# GPIO.net
KiCad netlist of a schematic drawn in Altium Designer
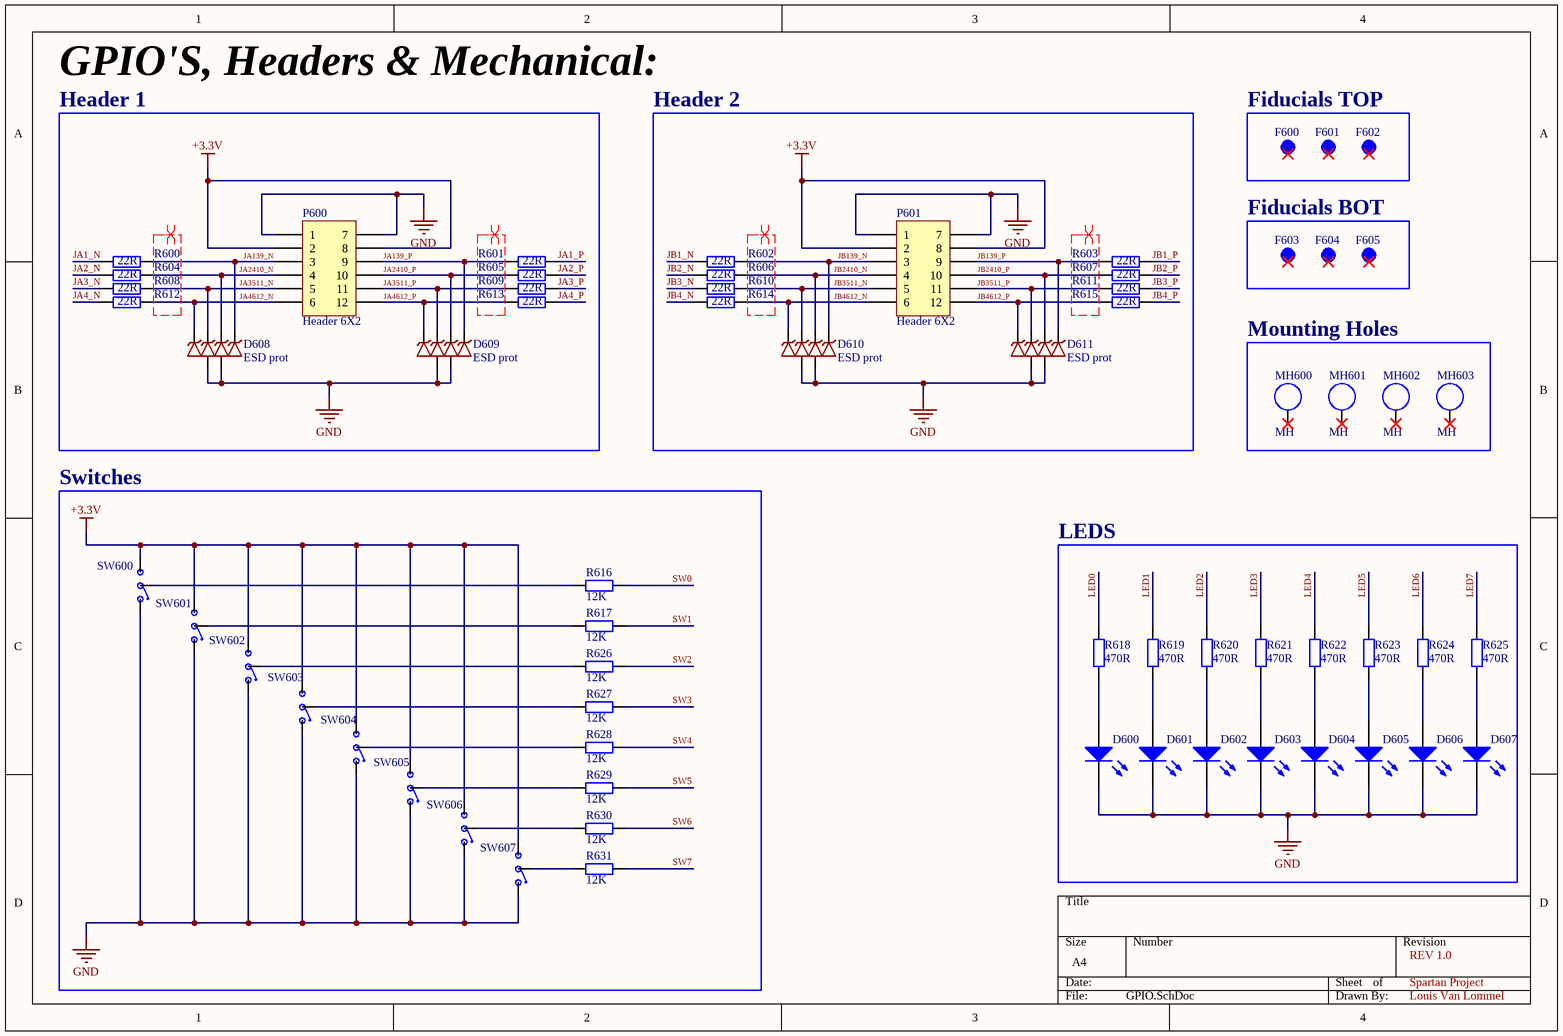
[diagram p0: GPIO.SchDoc]

(export (version "E")
  (design (tool "Eeschema 10.0.6"))
  (components
    (comp (ref "D600")
      (value "LED")
      (footprint "LED_0603")
      (description "Typical INFRARED GaAs LED")
      (fields (field (name "PUBLISHER") "Altium Limited"))
      (libsource (lib "Miscellaneous Devices") (part "LED0"))
    )
    (comp (ref "D601")
      (value "LED")
      (footprint "LED_0603")
      (description "Typical INFRARED GaAs LED")
      (fields (field (name "PUBLISHER") "Altium Limited"))
      (libsource (lib "Miscellaneous Devices") (part "LED0"))
    )
    (comp (ref "D602")
      (value "LED")
      (footprint "LED_0603")
      (description "Typical INFRARED GaAs LED")
      (fields (field (name "PUBLISHER") "Altium Limited"))
      (libsource (lib "Miscellaneous Devices") (part "LED0"))
    )
    (comp (ref "D603")
      (value "LED")
      (footprint "LED_0603")
      (description "Typical INFRARED GaAs LED")
      (fields (field (name "PUBLISHER") "Altium Limited"))
      (libsource (lib "Miscellaneous Devices") (part "LED0"))
    )
    (comp (ref "D604")
      (value "LED")
      (footprint "LED_0603")
      (description "Typical INFRARED GaAs LED")
      (fields (field (name "PUBLISHER") "Altium Limited"))
      (libsource (lib "Miscellaneous Devices") (part "LED0"))
    )
    (comp (ref "D605")
      (value "LED")
      (footprint "LED_0603")
      (description "Typical INFRARED GaAs LED")
      (fields (field (name "PUBLISHER") "Altium Limited"))
      (libsource (lib "Miscellaneous Devices") (part "LED0"))
    )
    (comp (ref "D606")
      (value "LED")
      (footprint "LED_0603")
      (description "Typical INFRARED GaAs LED")
      (fields (field (name "PUBLISHER") "Altium Limited"))
      (libsource (lib "Miscellaneous Devices") (part "LED0"))
    )
    (comp (ref "D607")
      (value "LED")
      (footprint "LED_0603")
      (description "Typical INFRARED GaAs LED")
      (fields (field (name "PUBLISHER") "Altium Limited"))
      (libsource (lib "Miscellaneous Devices") (part "LED0"))
    )
    (comp (ref "D608")
      (value "ESD prot")
      (footprint "SOT457")
      (description "NEXPERIA BZA462A,125")
      (libsource (lib "Schematic_Symbols") (part "ESD prot"))
    )
    (comp (ref "D609")
      (value "ESD prot")
      (footprint "SOT457")
      (description "NEXPERIA BZA462A,125")
      (libsource (lib "Schematic_Symbols") (part "ESD prot"))
    )
    (comp (ref "D610")
      (value "ESD prot")
      (footprint "SOT457")
      (description "NEXPERIA BZA462A,125")
      (libsource (lib "Schematic_Symbols") (part "ESD prot"))
    )
    (comp (ref "D611")
      (value "ESD prot")
      (footprint "SOT457")
      (description "NEXPERIA BZA462A,125")
      (libsource (lib "Schematic_Symbols") (part "ESD prot"))
    )
    (comp (ref "F600")
      (value "Fiducial")
      (footprint "Fiducial30mil")
      (description "30mil Fiducial")
      (libsource (lib "Schematic_Symbols") (part "Fiducial"))
    )
    (comp (ref "F601")
      (value "Fiducial")
      (footprint "Fiducial30mil")
      (description "30mil Fiducial")
      (libsource (lib "Schematic_Symbols") (part "Fiducial"))
    )
    (comp (ref "F602")
      (value "Fiducial")
      (footprint "Fiducial30mil")
      (description "30mil Fiducial")
      (libsource (lib "Schematic_Symbols") (part "Fiducial"))
    )
    (comp (ref "F603")
      (value "Fiducial")
      (footprint "Fiducial30mil")
      (description "30mil Fiducial")
      (libsource (lib "Schematic_Symbols") (part "Fiducial"))
    )
    (comp (ref "F604")
      (value "Fiducial")
      (footprint "Fiducial30mil")
      (description "30mil Fiducial")
      (libsource (lib "Schematic_Symbols") (part "Fiducial"))
    )
    (comp (ref "F605")
      (value "Fiducial")
      (footprint "Fiducial30mil")
      (description "30mil Fiducial")
      (libsource (lib "Schematic_Symbols") (part "Fiducial"))
    )
    (comp (ref "MH600")
      (value "MH")
      (footprint "MH3.2mm")
      (description "3.2mm mounting hole")
      (libsource (lib "Schematic_Symbols") (part "MH"))
    )
    (comp (ref "MH601")
      (value "MH")
      (footprint "MH3.2mm")
      (description "3.2mm mounting hole")
      (libsource (lib "Schematic_Symbols") (part "MH"))
    )
    (comp (ref "MH602")
      (value "MH")
      (footprint "MH3.2mm")
      (description "3.2mm mounting hole")
      (libsource (lib "Schematic_Symbols") (part "MH"))
    )
    (comp (ref "MH603")
      (value "MH")
      (footprint "MH3.2mm")
      (description "3.2mm mounting hole")
      (libsource (lib "Schematic_Symbols") (part "MH"))
    )
    (comp (ref "P600")
      (value "Header 6X2")
      (footprint "HDR2X6_CEN")
      (description "Header, 6-Pin, Dual row")
      (fields (field (name "PUBLISHER") "Altium Limited"))
      (libsource (lib "Miscellaneous Connectors") (part "Header 6X2A"))
    )
    (comp (ref "P601")
      (value "Header 6X2")
      (footprint "HDR2X6_CEN")
      (description "Header, 6-Pin, Dual row")
      (fields (field (name "PUBLISHER") "Altium Limited"))
      (libsource (lib "Miscellaneous Connectors") (part "Header 6X2A"))
    )
    (comp (ref "R600")
      (value "22R")
      (footprint "RES_0603")
      (description "Resistor")
      (fields (field (name "Comment") "22") (field (name "PUBLISHER") "Altium Limited"))
      (libsource (lib "Miscellaneous Devices") (part "Res2"))
    )
    (comp (ref "R601")
      (value "22R")
      (footprint "RES_0603")
      (description "Resistor")
      (fields (field (name "Comment") "22") (field (name "PUBLISHER") "Altium Limited"))
      (libsource (lib "Miscellaneous Devices") (part "Res2"))
    )
    (comp (ref "R602")
      (value "22R")
      (footprint "RES_0603")
      (description "Resistor")
      (fields (field (name "Comment") "22") (field (name "PUBLISHER") "Altium Limited"))
      (libsource (lib "Miscellaneous Devices") (part "Res2"))
    )
    (comp (ref "R603")
      (value "22R")
      (footprint "RES_0603")
      (description "Resistor")
      (fields (field (name "Comment") "22") (field (name "PUBLISHER") "Altium Limited"))
      (libsource (lib "Miscellaneous Devices") (part "Res2"))
    )
    (comp (ref "R604")
      (value "22R")
      (footprint "RES_0603")
      (description "Resistor")
      (fields (field (name "Comment") "22") (field (name "PUBLISHER") "Altium Limited"))
      (libsource (lib "Miscellaneous Devices") (part "Res2"))
    )
    (comp (ref "R605")
      (value "22R")
      (footprint "RES_0603")
      (description "Resistor")
      (fields (field (name "Comment") "22") (field (name "PUBLISHER") "Altium Limited"))
      (libsource (lib "Miscellaneous Devices") (part "Res2"))
    )
    (comp (ref "R606")
      (value "22R")
      (footprint "RES_0603")
      (description "Resistor")
      (fields (field (name "Comment") "22") (field (name "PUBLISHER") "Altium Limited"))
      (libsource (lib "Miscellaneous Devices") (part "Res2"))
    )
    (comp (ref "R607")
      (value "22R")
      (footprint "RES_0603")
      (description "Resistor")
      (fields (field (name "Comment") "22") (field (name "PUBLISHER") "Altium Limited"))
      (libsource (lib "Miscellaneous Devices") (part "Res2"))
    )
    (comp (ref "R608")
      (value "22R")
      (footprint "RES_0603")
      (description "Resistor")
      (fields (field (name "Comment") "22") (field (name "PUBLISHER") "Altium Limited"))
      (libsource (lib "Miscellaneous Devices") (part "Res2"))
    )
    (comp (ref "R609")
      (value "22R")
      (footprint "RES_0603")
      (description "Resistor")
      (fields (field (name "Comment") "22") (field (name "PUBLISHER") "Altium Limited"))
      (libsource (lib "Miscellaneous Devices") (part "Res2"))
    )
    (comp (ref "R610")
      (value "22R")
      (footprint "RES_0603")
      (description "Resistor")
      (fields (field (name "Comment") "22") (field (name "PUBLISHER") "Altium Limited"))
      (libsource (lib "Miscellaneous Devices") (part "Res2"))
    )
    (comp (ref "R611")
      (value "22R")
      (footprint "RES_0603")
      (description "Resistor")
      (fields (field (name "Comment") "22") (field (name "PUBLISHER") "Altium Limited"))
      (libsource (lib "Miscellaneous Devices") (part "Res2"))
    )
    (comp (ref "R612")
      (value "22R")
      (footprint "RES_0603")
      (description "Resistor")
      (fields (field (name "Comment") "22") (field (name "PUBLISHER") "Altium Limited"))
      (libsource (lib "Miscellaneous Devices") (part "Res2"))
    )
    (comp (ref "R613")
      (value "22R")
      (footprint "RES_0603")
      (description "Resistor")
      (fields (field (name "Comment") "22") (field (name "PUBLISHER") "Altium Limited"))
      (libsource (lib "Miscellaneous Devices") (part "Res2"))
    )
    (comp (ref "R614")
      (value "22R")
      (footprint "RES_0603")
      (description "Resistor")
      (fields (field (name "Comment") "22") (field (name "PUBLISHER") "Altium Limited"))
      (libsource (lib "Miscellaneous Devices") (part "Res2"))
    )
    (comp (ref "R615")
      (value "22R")
      (footprint "RES_0603")
      (description "Resistor")
      (fields (field (name "Comment") "22") (field (name "PUBLISHER") "Altium Limited"))
      (libsource (lib "Miscellaneous Devices") (part "Res2"))
    )
    (comp (ref "R616")
      (value "12K")
      (footprint "RES_0603")
      (description "Resistor")
      (fields (field (name "PUBLISHER") "Altium Limited"))
      (libsource (lib "Miscellaneous Devices") (part "Res2"))
    )
    (comp (ref "R617")
      (value "12K")
      (footprint "RES_0603")
      (description "Resistor")
      (fields (field (name "PUBLISHER") "Altium Limited"))
      (libsource (lib "Miscellaneous Devices") (part "Res2"))
    )
    (comp (ref "R618")
      (value "470R")
      (footprint "RES_0603")
      (description "Resistor")
      (fields (field (name "Comment") "470") (field (name "PUBLISHER") "Altium Limited"))
      (libsource (lib "") (part "Res2_1"))
    )
    (comp (ref "R619")
      (value "470R")
      (footprint "RES_0603")
      (description "Resistor")
      (fields (field (name "Comment") "470") (field (name "PUBLISHER") "Altium Limited"))
      (libsource (lib "") (part "Res2_1"))
    )
    (comp (ref "R620")
      (value "470R")
      (footprint "RES_0603")
      (description "Resistor")
      (fields (field (name "Comment") "470") (field (name "PUBLISHER") "Altium Limited"))
      (libsource (lib "") (part "Res2_1"))
    )
    (comp (ref "R621")
      (value "470R")
      (footprint "RES_0603")
      (description "Resistor")
      (fields (field (name "Comment") "470") (field (name "PUBLISHER") "Altium Limited"))
      (libsource (lib "") (part "Res2_1"))
    )
    (comp (ref "R622")
      (value "470R")
      (footprint "RES_0603")
      (description "Resistor")
      (fields (field (name "Comment") "470") (field (name "PUBLISHER") "Altium Limited"))
      (libsource (lib "") (part "Res2_1"))
    )
    (comp (ref "R623")
      (value "470R")
      (footprint "RES_0603")
      (description "Resistor")
      (fields (field (name "Comment") "470") (field (name "PUBLISHER") "Altium Limited"))
      (libsource (lib "") (part "Res2_1"))
    )
    (comp (ref "R624")
      (value "470R")
      (footprint "RES_0603")
      (description "Resistor")
      (fields (field (name "Comment") "470") (field (name "PUBLISHER") "Altium Limited"))
      (libsource (lib "") (part "Res2_1"))
    )
    (comp (ref "R625")
      (value "470R")
      (footprint "RES_0603")
      (description "Resistor")
      (fields (field (name "Comment") "470") (field (name "PUBLISHER") "Altium Limited"))
      (libsource (lib "") (part "Res2_1"))
    )
    (comp (ref "R626")
      (value "12K")
      (footprint "RES_0603")
      (description "Resistor")
      (fields (field (name "PUBLISHER") "Altium Limited"))
      (libsource (lib "Miscellaneous Devices") (part "Res2"))
    )
    (comp (ref "R627")
      (value "12K")
      (footprint "RES_0603")
      (description "Resistor")
      (fields (field (name "PUBLISHER") "Altium Limited"))
      (libsource (lib "Miscellaneous Devices") (part "Res2"))
    )
    (comp (ref "R628")
      (value "12K")
      (footprint "RES_0603")
      (description "Resistor")
      (fields (field (name "PUBLISHER") "Altium Limited"))
      (libsource (lib "Miscellaneous Devices") (part "Res2"))
    )
    (comp (ref "R629")
      (value "12K")
      (footprint "RES_0603")
      (description "Resistor")
      (fields (field (name "PUBLISHER") "Altium Limited"))
      (libsource (lib "Miscellaneous Devices") (part "Res2"))
    )
    (comp (ref "R630")
      (value "12K")
      (footprint "RES_0603")
      (description "Resistor")
      (fields (field (name "PUBLISHER") "Altium Limited"))
      (libsource (lib "Miscellaneous Devices") (part "Res2"))
    )
    (comp (ref "R631")
      (value "12K")
      (footprint "RES_0603")
      (description "Resistor")
      (fields (field (name "PUBLISHER") "Altium Limited"))
      (libsource (lib "Miscellaneous Devices") (part "Res2"))
    )
    (comp (ref "SW600")
      (value "SPDT SW")
      (footprint "SPDT SWITCH")
      (libsource (lib "Schematic_Symbols") (part "SPDT SW"))
    )
    (comp (ref "SW601")
      (value "SPDT SW")
      (footprint "SPDT SWITCH")
      (libsource (lib "Schematic_Symbols") (part "SPDT SW"))
    )
    (comp (ref "SW602")
      (value "SPDT SW")
      (footprint "SPDT SWITCH")
      (libsource (lib "Schematic_Symbols") (part "SPDT SW"))
    )
    (comp (ref "SW603")
      (value "SPDT SW")
      (footprint "SPDT SWITCH")
      (libsource (lib "Schematic_Symbols") (part "SPDT SW"))
    )
    (comp (ref "SW604")
      (value "SPDT SW")
      (footprint "SPDT SWITCH")
      (libsource (lib "Schematic_Symbols") (part "SPDT SW"))
    )
    (comp (ref "SW605")
      (value "SPDT SW")
      (footprint "SPDT SWITCH")
      (libsource (lib "Schematic_Symbols") (part "SPDT SW"))
    )
    (comp (ref "SW606")
      (value "SPDT SW")
      (footprint "SPDT SWITCH")
      (libsource (lib "Schematic_Symbols") (part "SPDT SW"))
    )
    (comp (ref "SW607")
      (value "SPDT SW")
      (footprint "SPDT SWITCH")
      (libsource (lib "Schematic_Symbols") (part "SPDT SW"))
    )
  )
  (nets
    (net (code "1") (name "+3.3V") (class "Default")
      (node (ref "P600") (pin "2") (pinfunction "2_2") (pintype "passive"))
      (node (ref "P600") (pin "8") (pinfunction "8_8") (pintype "passive"))
      (node (ref "P601") (pin "2") (pinfunction "2_2") (pintype "passive"))
      (node (ref "P601") (pin "8") (pinfunction "8_8") (pintype "passive"))
      (node (ref "SW600") (pin "1") (pinfunction "1_1") (pintype "passive"))
      (node (ref "SW601") (pin "1") (pinfunction "1_1") (pintype "passive"))
      (node (ref "SW602") (pin "1") (pinfunction "1_1") (pintype "passive"))
      (node (ref "SW603") (pin "1") (pinfunction "1_1") (pintype "passive"))
      (node (ref "SW604") (pin "1") (pinfunction "1_1") (pintype "passive"))
      (node (ref "SW605") (pin "1") (pinfunction "1_1") (pintype "passive"))
      (node (ref "SW606") (pin "1") (pinfunction "1_1") (pintype "passive"))
      (node (ref "SW607") (pin "1") (pinfunction "1_1") (pintype "passive"))
    )
    (net (code "2") (name "/JA1_N") (class "Default")
      (node (ref "R600") (pin "2") (pinfunction "2_2") (pintype "passive"))
    )
    (net (code "3") (name "/JA1_P") (class "Default")
      (node (ref "R601") (pin "1") (pinfunction "1_1") (pintype "passive"))
    )
    (net (code "4") (name "/JA2_N") (class "Default")
      (node (ref "R604") (pin "2") (pinfunction "2_2") (pintype "passive"))
    )
    (net (code "5") (name "/JA2_P") (class "Default")
      (node (ref "R605") (pin "1") (pinfunction "1_1") (pintype "passive"))
    )
    (net (code "6") (name "/JA3_N") (class "Default")
      (node (ref "R608") (pin "2") (pinfunction "2_2") (pintype "passive"))
    )
    (net (code "7") (name "/JA3_P") (class "Default")
      (node (ref "R609") (pin "1") (pinfunction "1_1") (pintype "passive"))
    )
    (net (code "8") (name "/JA4_N") (class "Default")
      (node (ref "R612") (pin "2") (pinfunction "2_2") (pintype "passive"))
    )
    (net (code "9") (name "/JA4_P") (class "Default")
      (node (ref "R613") (pin "1") (pinfunction "1_1") (pintype "passive"))
    )
    (net (code "10") (name "/JA139_N") (class "Default")
      (node (ref "D608") (pin "4") (pinfunction "4_4") (pintype "passive"))
      (node (ref "P600") (pin "3") (pinfunction "3_3") (pintype "passive"))
      (node (ref "R600") (pin "1") (pinfunction "1_1") (pintype "passive"))
    )
    (net (code "11") (name "/JA139_P") (class "Default")
      (node (ref "D609") (pin "4") (pinfunction "4_4") (pintype "passive"))
      (node (ref "P600") (pin "9") (pinfunction "9_9") (pintype "passive"))
      (node (ref "R601") (pin "2") (pinfunction "2_2") (pintype "passive"))
    )
    (net (code "12") (name "/JA2410_N") (class "Default")
      (node (ref "D608") (pin "3") (pinfunction "3_3") (pintype "passive"))
      (node (ref "P600") (pin "4") (pinfunction "4_4") (pintype "passive"))
      (node (ref "R604") (pin "1") (pinfunction "1_1") (pintype "passive"))
    )
    (net (code "13") (name "/JA2410_P") (class "Default")
      (node (ref "D609") (pin "3") (pinfunction "3_3") (pintype "passive"))
      (node (ref "P600") (pin "10") (pinfunction "10_10") (pintype "passive"))
      (node (ref "R605") (pin "2") (pinfunction "2_2") (pintype "passive"))
    )
    (net (code "14") (name "/JA3511_N") (class "Default")
      (node (ref "D608") (pin "2") (pinfunction "2_2") (pintype "passive"))
      (node (ref "P600") (pin "5") (pinfunction "5_5") (pintype "passive"))
      (node (ref "R608") (pin "1") (pinfunction "1_1") (pintype "passive"))
    )
    (net (code "15") (name "/JA3511_P") (class "Default")
      (node (ref "D609") (pin "2") (pinfunction "2_2") (pintype "passive"))
      (node (ref "P600") (pin "11") (pinfunction "11_11") (pintype "passive"))
      (node (ref "R609") (pin "2") (pinfunction "2_2") (pintype "passive"))
    )
    (net (code "16") (name "/JA4612_N") (class "Default")
      (node (ref "D608") (pin "1") (pinfunction "1_1") (pintype "passive"))
      (node (ref "P600") (pin "6") (pinfunction "6_6") (pintype "passive"))
      (node (ref "R612") (pin "1") (pinfunction "1_1") (pintype "passive"))
    )
    (net (code "17") (name "/JA4612_P") (class "Default")
      (node (ref "D609") (pin "1") (pinfunction "1_1") (pintype "passive"))
      (node (ref "P600") (pin "12") (pinfunction "12_12") (pintype "passive"))
      (node (ref "R613") (pin "2") (pinfunction "2_2") (pintype "passive"))
    )
    (net (code "18") (name "/JB1_N") (class "Default")
      (node (ref "R602") (pin "2") (pinfunction "2_2") (pintype "passive"))
    )
    (net (code "19") (name "/JB1_P") (class "Default")
      (node (ref "R603") (pin "1") (pinfunction "1_1") (pintype "passive"))
    )
    (net (code "20") (name "/JB2_N") (class "Default")
      (node (ref "R606") (pin "2") (pinfunction "2_2") (pintype "passive"))
    )
    (net (code "21") (name "/JB2_P") (class "Default")
      (node (ref "R607") (pin "1") (pinfunction "1_1") (pintype "passive"))
    )
    (net (code "22") (name "/JB3_N") (class "Default")
      (node (ref "R610") (pin "2") (pinfunction "2_2") (pintype "passive"))
    )
    (net (code "23") (name "/JB3_P") (class "Default")
      (node (ref "R611") (pin "1") (pinfunction "1_1") (pintype "passive"))
    )
    (net (code "24") (name "/JB4_N") (class "Default")
      (node (ref "R614") (pin "2") (pinfunction "2_2") (pintype "passive"))
    )
    (net (code "25") (name "/JB4_P") (class "Default")
      (node (ref "R615") (pin "1") (pinfunction "1_1") (pintype "passive"))
    )
    (net (code "26") (name "/JB139_N") (class "Default")
      (node (ref "D610") (pin "4") (pinfunction "4_4") (pintype "passive"))
      (node (ref "P601") (pin "3") (pinfunction "3_3") (pintype "passive"))
      (node (ref "R602") (pin "1") (pinfunction "1_1") (pintype "passive"))
    )
    (net (code "27") (name "/JB139_P") (class "Default")
      (node (ref "D611") (pin "4") (pinfunction "4_4") (pintype "passive"))
      (node (ref "P601") (pin "9") (pinfunction "9_9") (pintype "passive"))
      (node (ref "R603") (pin "2") (pinfunction "2_2") (pintype "passive"))
    )
    (net (code "28") (name "/JB2410_N") (class "Default")
      (node (ref "D610") (pin "3") (pinfunction "3_3") (pintype "passive"))
      (node (ref "P601") (pin "4") (pinfunction "4_4") (pintype "passive"))
      (node (ref "R606") (pin "1") (pinfunction "1_1") (pintype "passive"))
    )
    (net (code "29") (name "/JB2410_P") (class "Default")
      (node (ref "D611") (pin "3") (pinfunction "3_3") (pintype "passive"))
      (node (ref "P601") (pin "10") (pinfunction "10_10") (pintype "passive"))
      (node (ref "R607") (pin "2") (pinfunction "2_2") (pintype "passive"))
    )
    (net (code "30") (name "/JB3511_N") (class "Default")
      (node (ref "D610") (pin "2") (pinfunction "2_2") (pintype "passive"))
      (node (ref "P601") (pin "5") (pinfunction "5_5") (pintype "passive"))
      (node (ref "R610") (pin "1") (pinfunction "1_1") (pintype "passive"))
    )
    (net (code "31") (name "/JB3511_P") (class "Default")
      (node (ref "D611") (pin "2") (pinfunction "2_2") (pintype "passive"))
      (node (ref "P601") (pin "11") (pinfunction "11_11") (pintype "passive"))
      (node (ref "R611") (pin "2") (pinfunction "2_2") (pintype "passive"))
    )
    (net (code "32") (name "/JB4612_N") (class "Default")
      (node (ref "D610") (pin "1") (pinfunction "1_1") (pintype "passive"))
      (node (ref "P601") (pin "6") (pinfunction "6_6") (pintype "passive"))
      (node (ref "R614") (pin "1") (pinfunction "1_1") (pintype "passive"))
    )
    (net (code "33") (name "/JB4612_P") (class "Default")
      (node (ref "D611") (pin "1") (pinfunction "1_1") (pintype "passive"))
      (node (ref "P601") (pin "12") (pinfunction "12_12") (pintype "passive"))
      (node (ref "R615") (pin "2") (pinfunction "2_2") (pintype "passive"))
    )
    (net (code "34") (name "/LED0") (class "Default")
      (node (ref "R618") (pin "2") (pinfunction "2_2") (pintype "passive"))
    )
    (net (code "35") (name "/LED1") (class "Default")
      (node (ref "R619") (pin "2") (pinfunction "2_2") (pintype "passive"))
    )
    (net (code "36") (name "/LED2") (class "Default")
      (node (ref "R620") (pin "2") (pinfunction "2_2") (pintype "passive"))
    )
    (net (code "37") (name "/LED3") (class "Default")
      (node (ref "R621") (pin "2") (pinfunction "2_2") (pintype "passive"))
    )
    (net (code "38") (name "/LED4") (class "Default")
      (node (ref "R622") (pin "2") (pinfunction "2_2") (pintype "passive"))
    )
    (net (code "39") (name "/LED5") (class "Default")
      (node (ref "R623") (pin "2") (pinfunction "2_2") (pintype "passive"))
    )
    (net (code "40") (name "/LED6") (class "Default")
      (node (ref "R624") (pin "2") (pinfunction "2_2") (pintype "passive"))
    )
    (net (code "41") (name "/LED7") (class "Default")
      (node (ref "R625") (pin "2") (pinfunction "2_2") (pintype "passive"))
    )
    (net (code "42") (name "/SW0") (class "Default")
      (node (ref "R616") (pin "1") (pinfunction "1_1") (pintype "passive"))
    )
    (net (code "43") (name "/SW1") (class "Default")
      (node (ref "R617") (pin "1") (pinfunction "1_1") (pintype "passive"))
    )
    (net (code "44") (name "/SW2") (class "Default")
      (node (ref "R626") (pin "1") (pinfunction "1_1") (pintype "passive"))
    )
    (net (code "45") (name "/SW3") (class "Default")
      (node (ref "R627") (pin "1") (pinfunction "1_1") (pintype "passive"))
    )
    (net (code "46") (name "/SW4") (class "Default")
      (node (ref "R628") (pin "1") (pinfunction "1_1") (pintype "passive"))
    )
    (net (code "47") (name "/SW5") (class "Default")
      (node (ref "R629") (pin "1") (pinfunction "1_1") (pintype "passive"))
    )
    (net (code "48") (name "/SW6") (class "Default")
      (node (ref "R630") (pin "1") (pinfunction "1_1") (pintype "passive"))
    )
    (net (code "49") (name "/SW7") (class "Default")
      (node (ref "R631") (pin "1") (pinfunction "1_1") (pintype "passive"))
    )
    (net (code "50") (name "GND") (class "Default")
      (node (ref "D600") (pin "2") (pinfunction "K_2") (pintype "passive"))
      (node (ref "D601") (pin "2") (pinfunction "K_2") (pintype "passive"))
      (node (ref "D602") (pin "2") (pinfunction "K_2") (pintype "passive"))
      (node (ref "D603") (pin "2") (pinfunction "K_2") (pintype "passive"))
      (node (ref "D604") (pin "2") (pinfunction "K_2") (pintype "passive"))
      (node (ref "D605") (pin "2") (pinfunction "K_2") (pintype "passive"))
      (node (ref "D606") (pin "2") (pinfunction "K_2") (pintype "passive"))
      (node (ref "D607") (pin "2") (pinfunction "K_2") (pintype "passive"))
      (node (ref "D608") (pin "5") (pinfunction "5_5") (pintype "passive"))
      (node (ref "D608") (pin "6") (pinfunction "6_6") (pintype "passive"))
      (node (ref "D609") (pin "5") (pinfunction "5_5") (pintype "passive"))
      (node (ref "D609") (pin "6") (pinfunction "6_6") (pintype "passive"))
      (node (ref "D610") (pin "5") (pinfunction "5_5") (pintype "passive"))
      (node (ref "D610") (pin "6") (pinfunction "6_6") (pintype "passive"))
      (node (ref "D611") (pin "5") (pinfunction "5_5") (pintype "passive"))
      (node (ref "D611") (pin "6") (pinfunction "6_6") (pintype "passive"))
      (node (ref "P600") (pin "1") (pinfunction "1_1") (pintype "passive"))
      (node (ref "P600") (pin "7") (pinfunction "7_7") (pintype "passive"))
      (node (ref "P601") (pin "1") (pinfunction "1_1") (pintype "passive"))
      (node (ref "P601") (pin "7") (pinfunction "7_7") (pintype "passive"))
      (node (ref "SW600") (pin "3") (pinfunction "3_3") (pintype "passive"))
      (node (ref "SW601") (pin "3") (pinfunction "3_3") (pintype "passive"))
      (node (ref "SW602") (pin "3") (pinfunction "3_3") (pintype "passive"))
      (node (ref "SW603") (pin "3") (pinfunction "3_3") (pintype "passive"))
      (node (ref "SW604") (pin "3") (pinfunction "3_3") (pintype "passive"))
      (node (ref "SW605") (pin "3") (pinfunction "3_3") (pintype "passive"))
      (node (ref "SW606") (pin "3") (pinfunction "3_3") (pintype "passive"))
      (node (ref "SW607") (pin "3") (pinfunction "3_3") (pintype "passive"))
    )
    (net (code "51") (name "Net-(D600-A)") (class "Default")
      (node (ref "D600") (pin "1") (pinfunction "A_1") (pintype "passive"))
      (node (ref "R618") (pin "1") (pinfunction "1_1") (pintype "passive"))
    )
    (net (code "52") (name "Net-(D601-A)") (class "Default")
      (node (ref "D601") (pin "1") (pinfunction "A_1") (pintype "passive"))
      (node (ref "R619") (pin "1") (pinfunction "1_1") (pintype "passive"))
    )
    (net (code "53") (name "Net-(D602-A)") (class "Default")
      (node (ref "D602") (pin "1") (pinfunction "A_1") (pintype "passive"))
      (node (ref "R620") (pin "1") (pinfunction "1_1") (pintype "passive"))
    )
    (net (code "54") (name "Net-(D603-A)") (class "Default")
      (node (ref "D603") (pin "1") (pinfunction "A_1") (pintype "passive"))
      (node (ref "R621") (pin "1") (pinfunction "1_1") (pintype "passive"))
    )
    (net (code "55") (name "Net-(D604-A)") (class "Default")
      (node (ref "D604") (pin "1") (pinfunction "A_1") (pintype "passive"))
      (node (ref "R622") (pin "1") (pinfunction "1_1") (pintype "passive"))
    )
    (net (code "56") (name "Net-(D605-A)") (class "Default")
      (node (ref "D605") (pin "1") (pinfunction "A_1") (pintype "passive"))
      (node (ref "R623") (pin "1") (pinfunction "1_1") (pintype "passive"))
    )
    (net (code "57") (name "Net-(D606-A)") (class "Default")
      (node (ref "D606") (pin "1") (pinfunction "A_1") (pintype "passive"))
      (node (ref "R624") (pin "1") (pinfunction "1_1") (pintype "passive"))
    )
    (net (code "58") (name "Net-(D607-A)") (class "Default")
      (node (ref "D607") (pin "1") (pinfunction "A_1") (pintype "passive"))
      (node (ref "R625") (pin "1") (pinfunction "1_1") (pintype "passive"))
    )
    (net (code "59") (name "Net-(R616-Pad2)") (class "Default")
      (node (ref "R616") (pin "2") (pinfunction "2_2") (pintype "passive"))
      (node (ref "SW600") (pin "2") (pinfunction "2_2") (pintype "passive"))
    )
    (net (code "60") (name "Net-(R617-Pad2)") (class "Default")
      (node (ref "R617") (pin "2") (pinfunction "2_2") (pintype "passive"))
      (node (ref "SW601") (pin "2") (pinfunction "2_2") (pintype "passive"))
    )
    (net (code "61") (name "Net-(R626-Pad2)") (class "Default")
      (node (ref "R626") (pin "2") (pinfunction "2_2") (pintype "passive"))
      (node (ref "SW602") (pin "2") (pinfunction "2_2") (pintype "passive"))
    )
    (net (code "62") (name "Net-(R627-Pad2)") (class "Default")
      (node (ref "R627") (pin "2") (pinfunction "2_2") (pintype "passive"))
      (node (ref "SW603") (pin "2") (pinfunction "2_2") (pintype "passive"))
    )
    (net (code "63") (name "Net-(R628-Pad2)") (class "Default")
      (node (ref "R628") (pin "2") (pinfunction "2_2") (pintype "passive"))
      (node (ref "SW604") (pin "2") (pinfunction "2_2") (pintype "passive"))
    )
    (net (code "64") (name "Net-(R629-Pad2)") (class "Default")
      (node (ref "R629") (pin "2") (pinfunction "2_2") (pintype "passive"))
      (node (ref "SW605") (pin "2") (pinfunction "2_2") (pintype "passive"))
    )
    (net (code "65") (name "Net-(R630-Pad2)") (class "Default")
      (node (ref "R630") (pin "2") (pinfunction "2_2") (pintype "passive"))
      (node (ref "SW606") (pin "2") (pinfunction "2_2") (pintype "passive"))
    )
    (net (code "66") (name "Net-(R631-Pad2)") (class "Default")
      (node (ref "R631") (pin "2") (pinfunction "2_2") (pintype "passive"))
      (node (ref "SW607") (pin "2") (pinfunction "2_2") (pintype "passive"))
    )
    (net (code "67") (name "unconnected-(F600-Pad1)") (class "Default")
      (node (ref "F600") (pin "1") (pinfunction "1_1") (pintype "passive+no_connect"))
    )
    (net (code "68") (name "unconnected-(F601-Pad1)") (class "Default")
      (node (ref "F601") (pin "1") (pinfunction "1_1") (pintype "passive+no_connect"))
    )
    (net (code "69") (name "unconnected-(F602-Pad1)") (class "Default")
      (node (ref "F602") (pin "1") (pinfunction "1_1") (pintype "passive+no_connect"))
    )
    (net (code "70") (name "unconnected-(F603-Pad1)") (class "Default")
      (node (ref "F603") (pin "1") (pinfunction "1_1") (pintype "passive+no_connect"))
    )
    (net (code "71") (name "unconnected-(F604-Pad1)") (class "Default")
      (node (ref "F604") (pin "1") (pinfunction "1_1") (pintype "passive+no_connect"))
    )
    (net (code "72") (name "unconnected-(F605-Pad1)") (class "Default")
      (node (ref "F605") (pin "1") (pinfunction "1_1") (pintype "passive+no_connect"))
    )
    (net (code "73") (name "unconnected-(MH600-Pad1)") (class "Default")
      (node (ref "MH600") (pin "1") (pinfunction "1_1") (pintype "passive+no_connect"))
    )
    (net (code "74") (name "unconnected-(MH601-Pad1)") (class "Default")
      (node (ref "MH601") (pin "1") (pinfunction "1_1") (pintype "passive+no_connect"))
    )
    (net (code "75") (name "unconnected-(MH602-Pad1)") (class "Default")
      (node (ref "MH602") (pin "1") (pinfunction "1_1") (pintype "passive+no_connect"))
    )
    (net (code "76") (name "unconnected-(MH603-Pad1)") (class "Default")
      (node (ref "MH603") (pin "1") (pinfunction "1_1") (pintype "passive+no_connect"))
    )
  )
)
